# bacchus2.net
KiCad netlist of a schematic drawn in EAGLE
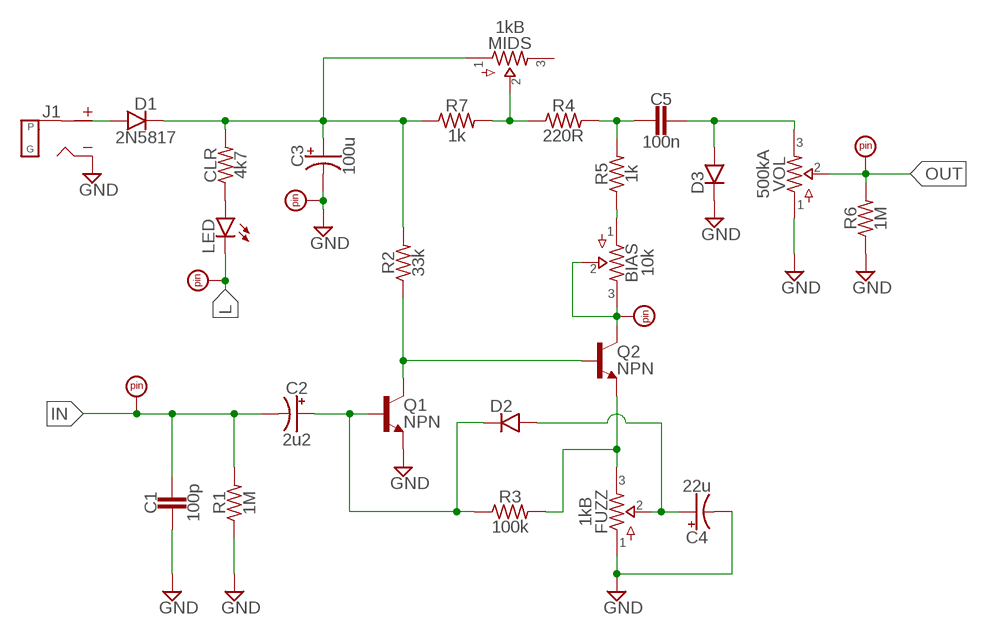
[diagram p0: schematic, sheet 1]

(export (version "E")
  (design (tool "Eeschema 10.0.6"))
  (components
    (comp (ref "BIAS")
      (value "10k")
      (footprint "eagle-import:2262_TRIM")
      (libsource (lib "eagle-import") (part "POTSTRIM"))
    )
    (comp (ref "C1")
      (value "100p")
      (footprint "eagle-import:050X030_025_2")
      (libsource (lib "eagle-import") (part "CER/FILM2"))
    )
    (comp (ref "C2")
      (value "2u2")
      (footprint "eagle-import:050_020_1")
      (libsource (lib "eagle-import") (part "0501"))
    )
    (comp (ref "C3")
      (value "100u")
      (footprint "eagle-import:050_020_1")
      (libsource (lib "eagle-import") (part "0501"))
    )
    (comp (ref "C4")
      (value "22u")
      (footprint "eagle-import:050_020_1")
      (libsource (lib "eagle-import") (part "0501"))
    )
    (comp (ref "C5")
      (value "100n")
      (footprint "eagle-import:050X030_025_2")
      (libsource (lib "eagle-import") (part "CER/FILM2"))
    )
    (comp (ref "CLR")
      (value "4k7")
      (footprint "eagle-import:R0207_3")
      (libsource (lib "eagle-import") (part "R_.3B"))
    )
    (comp (ref "D1")
      (value "2N5817")
      (footprint "eagle-import:DO41-3")
      (libsource (lib "eagle-import") (part "DO41.3"))
    )
    (comp (ref "D2")
      (value "DO35.2")
      (footprint "eagle-import:DO35-2")
      (libsource (lib "eagle-import") (part "DO35.2"))
    )
    (comp (ref "D3")
      (value "DO35.2")
      (footprint "eagle-import:DO35-2")
      (libsource (lib "eagle-import") (part "DO35.2"))
    )
    (comp (ref "FUZZ")
      (value "1kB")
      (footprint "eagle-import:9MM_W_MOUNTS")
      (libsource (lib "eagle-import") (part "POTS9MM_MOUNTED"))
    )
    (comp (ref "GND")
      (value "PADRND")
      (footprint "eagle-import:ROUND")
      (libsource (lib "eagle-import") (part "PADRND"))
    )
    (comp (ref "IN")
      (value "PADSQR")
      (footprint "eagle-import:SQUARE")
      (libsource (lib "eagle-import") (part "PADSQR"))
    )
    (comp (ref "J1")
      (value "DC_MONO")
      (footprint "eagle-import:DC")
      (libsource (lib "eagle-import") (part "DC_MONO"))
    )
    (comp (ref "L")
      (value "PADRND")
      (footprint "eagle-import:ROUND")
      (libsource (lib "eagle-import") (part "PADRND"))
    )
    (comp (ref "LED")
      (value "LEDB")
      (footprint "eagle-import:3MM_B")
      (libsource (lib "eagle-import") (part "LEDB"))
    )
    (comp (ref "MIDS")
      (value "1kB")
      (footprint "eagle-import:9MM_W_MOUNTS")
      (libsource (lib "eagle-import") (part "POTS9MM_MOUNTED"))
    )
    (comp (ref "OUT")
      (value "PADSQR")
      (footprint "eagle-import:SQUARE")
      (libsource (lib "eagle-import") (part "PADSQR"))
    )
    (comp (ref "Q1")
      (value "NPN")
      (footprint "eagle-import:TO5")
      (libsource (lib "eagle-import") (part "2N1306"))
    )
    (comp (ref "Q2")
      (value "NPN")
      (footprint "eagle-import:TO5")
      (libsource (lib "eagle-import") (part "2N1306"))
    )
    (comp (ref "R1")
      (value "1M")
      (footprint "eagle-import:R0207_3")
      (libsource (lib "eagle-import") (part "R_.3B"))
    )
    (comp (ref "R2")
      (value "33k")
      (footprint "eagle-import:R0207_3")
      (libsource (lib "eagle-import") (part "R_.3B"))
    )
    (comp (ref "R3")
      (value "100k")
      (footprint "eagle-import:R0207_3")
      (libsource (lib "eagle-import") (part "R_.3B"))
    )
    (comp (ref "R4")
      (value "220R")
      (footprint "eagle-import:R0207_3")
      (libsource (lib "eagle-import") (part "R_.3B"))
    )
    (comp (ref "R5")
      (value "1k")
      (footprint "eagle-import:R0207_3")
      (libsource (lib "eagle-import") (part "R_.3B"))
    )
    (comp (ref "R6")
      (value "1M")
      (footprint "eagle-import:R0207_3")
      (libsource (lib "eagle-import") (part "R_.3B"))
    )
    (comp (ref "R7")
      (value "1k")
      (footprint "eagle-import:R0207_3")
      (libsource (lib "eagle-import") (part "R_.3B"))
    )
    (comp (ref "TP")
      (value "PADSQR")
      (footprint "eagle-import:SQUARE")
      (libsource (lib "eagle-import") (part "PADSQR"))
    )
    (comp (ref "VOL")
      (value "500kA")
      (footprint "eagle-import:9MM_W_MOUNTS")
      (libsource (lib "eagle-import") (part "POTS9MM_MOUNTED"))
    )
  )
  (nets
    (net (code "1") (name "GND") (class "Default")
      (node (ref "C1") (pin "2") (pinfunction "2_2") (pintype "passive"))
      (node (ref "C3") (pin "-") (pinfunction "-_-") (pintype "passive"))
      (node (ref "C4") (pin "-") (pinfunction "-_-") (pintype "passive"))
      (node (ref "D3") (pin "C") (pinfunction "C_C") (pintype "passive"))
      (node (ref "FUZZ") (pin "P$1") (pinfunction "1_P$1") (pintype "passive"))
      (node (ref "GND") (pin "1") (pinfunction "P$1_1") (pintype "bidirectional"))
      (node (ref "J1") (pin "S") (pinfunction "SLEEVE_S") (pintype "passive"))
      (node (ref "Q1") (pin "1") (pinfunction "E_1") (pintype "passive"))
      (node (ref "R1") (pin "1") (pinfunction "1_1") (pintype "passive"))
      (node (ref "R6") (pin "1") (pinfunction "1_1") (pintype "passive"))
      (node (ref "VOL") (pin "P$1") (pinfunction "1_P$1") (pintype "passive"))
    )
    (net (code "2") (name "IN") (class "Default")
      (node (ref "C1") (pin "1") (pinfunction "1_1") (pintype "passive"))
      (node (ref "C2") (pin "-") (pinfunction "-_-") (pintype "passive"))
      (node (ref "IN") (pin "1") (pinfunction "P$1_1") (pintype "bidirectional"))
      (node (ref "R1") (pin "2") (pinfunction "2_2") (pintype "passive"))
    )
    (net (code "3") (name "L") (class "Default")
      (node (ref "L") (pin "1") (pinfunction "P$1_1") (pintype "bidirectional"))
      (node (ref "LED") (pin "K") (pinfunction "C_K") (pintype "passive"))
    )
    (net (code "4") (name "Net-(BIAS-Pad1)") (class "Default")
      (node (ref "BIAS") (pin "1") (pinfunction "1_1") (pintype "passive"))
      (node (ref "R5") (pin "1") (pinfunction "1_1") (pintype "passive"))
    )
    (net (code "5") (name "Net-(C5-Pad2)") (class "Default")
      (node (ref "C5") (pin "2") (pinfunction "2_2") (pintype "passive"))
      (node (ref "R4") (pin "2") (pinfunction "2_2") (pintype "passive"))
      (node (ref "R5") (pin "2") (pinfunction "2_2") (pintype "passive"))
    )
    (net (code "6") (name "Net-(CLR-Pad1)") (class "Default")
      (node (ref "CLR") (pin "1") (pinfunction "1_1") (pintype "passive"))
      (node (ref "LED") (pin "A") (pinfunction "A_A") (pintype "passive"))
    )
    (net (code "7") (name "Net-(FUZZ-2)") (class "Default")
      (node (ref "C4") (pin "+") (pinfunction "+_+") (pintype "passive"))
      (node (ref "D2") (pin "A") (pinfunction "A_A") (pintype "passive"))
      (node (ref "FUZZ") (pin "P$2") (pinfunction "2_P$2") (pintype "passive"))
    )
    (net (code "8") (name "Net-(FUZZ-3)") (class "Default")
      (node (ref "FUZZ") (pin "P$3") (pinfunction "3_P$3") (pintype "passive"))
      (node (ref "Q2") (pin "1") (pinfunction "E_1") (pintype "passive"))
      (node (ref "R3") (pin "2") (pinfunction "2_2") (pintype "passive"))
    )
    (net (code "9") (name "Net-(J1-TIP)") (class "Default")
      (node (ref "D1") (pin "A") (pinfunction "A_A") (pintype "passive"))
      (node (ref "J1") (pin "T") (pinfunction "TIP_T") (pintype "passive"))
    )
    (net (code "10") (name "Net-(MIDS-1)") (class "Default")
      (node (ref "C3") (pin "+") (pinfunction "+_+") (pintype "passive"))
      (node (ref "CLR") (pin "2") (pinfunction "2_2") (pintype "passive"))
      (node (ref "D1") (pin "C") (pinfunction "C_C") (pintype "passive"))
      (node (ref "MIDS") (pin "P$1") (pinfunction "1_P$1") (pintype "passive"))
      (node (ref "R2") (pin "2") (pinfunction "2_2") (pintype "passive"))
      (node (ref "R7") (pin "1") (pinfunction "1_1") (pintype "passive"))
    )
    (net (code "11") (name "Net-(MIDS-2)") (class "Default")
      (node (ref "MIDS") (pin "P$2") (pinfunction "2_P$2") (pintype "passive"))
      (node (ref "R4") (pin "1") (pinfunction "1_1") (pintype "passive"))
      (node (ref "R7") (pin "2") (pinfunction "2_2") (pintype "passive"))
    )
    (net (code "12") (name "Net-(Q1-B)") (class "Default")
      (node (ref "C2") (pin "+") (pinfunction "+_+") (pintype "passive"))
      (node (ref "D2") (pin "C") (pinfunction "C_C") (pintype "passive"))
      (node (ref "Q1") (pin "2") (pinfunction "B_2") (pintype "passive"))
      (node (ref "R3") (pin "1") (pinfunction "1_1") (pintype "passive"))
    )
    (net (code "13") (name "Net-(Q1-C)") (class "Default")
      (node (ref "Q1") (pin "3") (pinfunction "C_3") (pintype "passive"))
      (node (ref "Q2") (pin "2") (pinfunction "B_2") (pintype "passive"))
      (node (ref "R2") (pin "1") (pinfunction "1_1") (pintype "passive"))
    )
    (net (code "14") (name "Net-(Q2-C)") (class "Default")
      (node (ref "BIAS") (pin "2") (pinfunction "2_2") (pintype "passive"))
      (node (ref "BIAS") (pin "3") (pinfunction "3_3") (pintype "passive"))
      (node (ref "Q2") (pin "3") (pinfunction "C_3") (pintype "passive"))
      (node (ref "TP") (pin "1") (pinfunction "P$1_1") (pintype "bidirectional"))
    )
    (net (code "15") (name "Net-(VOL-3)") (class "Default")
      (node (ref "C5") (pin "1") (pinfunction "1_1") (pintype "passive"))
      (node (ref "D3") (pin "A") (pinfunction "A_A") (pintype "passive"))
      (node (ref "VOL") (pin "P$3") (pinfunction "3_P$3") (pintype "passive"))
    )
    (net (code "16") (name "OUT") (class "Default")
      (node (ref "OUT") (pin "1") (pinfunction "P$1_1") (pintype "bidirectional"))
      (node (ref "R6") (pin "2") (pinfunction "2_2") (pintype "passive"))
      (node (ref "VOL") (pin "P$2") (pinfunction "2_P$2") (pintype "passive"))
    )
    (net (code "17") (name "unconnected-(MIDS-3-PadP$3)") (class "Default")
      (node (ref "MIDS") (pin "P$3") (pinfunction "3_P$3") (pintype "passive"))
    )
  )
)
